# 2m_bandpass.net
KiCad netlist of a schematic drawn in EAGLE
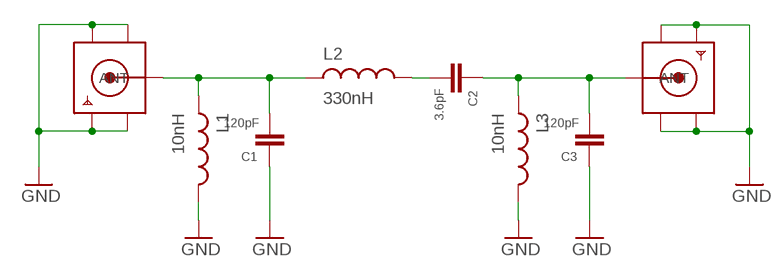
[diagram p0: schematic, sheet 1]

(export (version "E")
  (design (tool "Eeschema 10.0.6"))
  (components
    (comp (ref "C1")
      (value "120pF")
      (footprint "eagle-import:0805")
      (libsource (lib "eagle-import") (part "0805CAP"))
    )
    (comp (ref "C2")
      (value "3.6pF")
      (footprint "eagle-import:0805")
      (libsource (lib "eagle-import") (part "0805CAP"))
    )
    (comp (ref "C3")
      (value "120pF")
      (footprint "eagle-import:0805")
      (libsource (lib "eagle-import") (part "0805CAP"))
    )
    (comp (ref "L1")
      (value "10nH")
      (footprint "eagle-import:1008INDUCTOR")
      (libsource (lib "eagle-import") (part "1008INDUCTOR"))
    )
    (comp (ref "L2")
      (value "330nH")
      (footprint "eagle-import:1008INDUCTOR")
      (libsource (lib "eagle-import") (part "1008INDUCTOR"))
    )
    (comp (ref "L3")
      (value "10nH")
      (footprint "eagle-import:1008INDUCTOR")
      (libsource (lib "eagle-import") (part "1008INDUCTOR"))
    )
    (comp (ref "X1")
      (value "SMACONNECTOR_EDGE")
      (footprint "eagle-import:SMA_EDGELAUNCH")
      (libsource (lib "eagle-import") (part "SMACONNECTOR_EDGE"))
    )
    (comp (ref "X2")
      (value "SMACONNECTOR_EDGE")
      (footprint "eagle-import:SMA_EDGELAUNCH")
      (libsource (lib "eagle-import") (part "SMACONNECTOR_EDGE"))
    )
  )
  (nets
    (net (code "1") (name "GND") (class "Default")
      (node (ref "C1") (pin "P$2") (pinfunction "P$2_P$2") (pintype "bidirectional"))
      (node (ref "C3") (pin "P$2") (pinfunction "P$2_P$2") (pintype "bidirectional"))
      (node (ref "L1") (pin "P$2") (pinfunction "P$2_P$2") (pintype "bidirectional"))
      (node (ref "L3") (pin "P$2") (pinfunction "P$2_P$2") (pintype "bidirectional"))
      (node (ref "X1") (pin "GND@1") (pinfunction "GND4_GND@1") (pintype "power_in"))
      (node (ref "X1") (pin "GND@2") (pinfunction "GND3_GND@2") (pintype "power_in"))
      (node (ref "X1") (pin "GND@3") (pinfunction "GND2_GND@3") (pintype "power_in"))
      (node (ref "X1") (pin "GND@4") (pinfunction "GND1_GND@4") (pintype "power_in"))
      (node (ref "X2") (pin "GND@1") (pinfunction "GND4_GND@1") (pintype "power_in"))
      (node (ref "X2") (pin "GND@2") (pinfunction "GND3_GND@2") (pintype "power_in"))
      (node (ref "X2") (pin "GND@3") (pinfunction "GND2_GND@3") (pintype "power_in"))
      (node (ref "X2") (pin "GND@4") (pinfunction "GND1_GND@4") (pintype "power_in"))
    )
    (net (code "2") (name "Net-(C2-PadP$1)") (class "Default")
      (node (ref "C2") (pin "P$1") (pinfunction "P$1_P$1") (pintype "bidirectional"))
      (node (ref "L2") (pin "P$2") (pinfunction "P$2_P$2") (pintype "bidirectional"))
    )
    (net (code "3") (name "Net-(X1-ANT)") (class "Default")
      (node (ref "C1") (pin "P$1") (pinfunction "P$1_P$1") (pintype "bidirectional"))
      (node (ref "L1") (pin "P$1") (pinfunction "P$1_P$1") (pintype "bidirectional"))
      (node (ref "L2") (pin "P$1") (pinfunction "P$1_P$1") (pintype "bidirectional"))
      (node (ref "X1") (pin "P") (pinfunction "ANT_P") (pintype "bidirectional"))
    )
    (net (code "4") (name "Net-(X2-ANT)") (class "Default")
      (node (ref "C2") (pin "P$2") (pinfunction "P$2_P$2") (pintype "bidirectional"))
      (node (ref "C3") (pin "P$1") (pinfunction "P$1_P$1") (pintype "bidirectional"))
      (node (ref "L3") (pin "P$1") (pinfunction "P$1_P$1") (pintype "bidirectional"))
      (node (ref "X2") (pin "P") (pinfunction "ANT_P") (pintype "bidirectional"))
    )
  )
)
